# MyRollerShutter_rfm_1-3.net
KiCad netlist of a schematic drawn in EAGLE
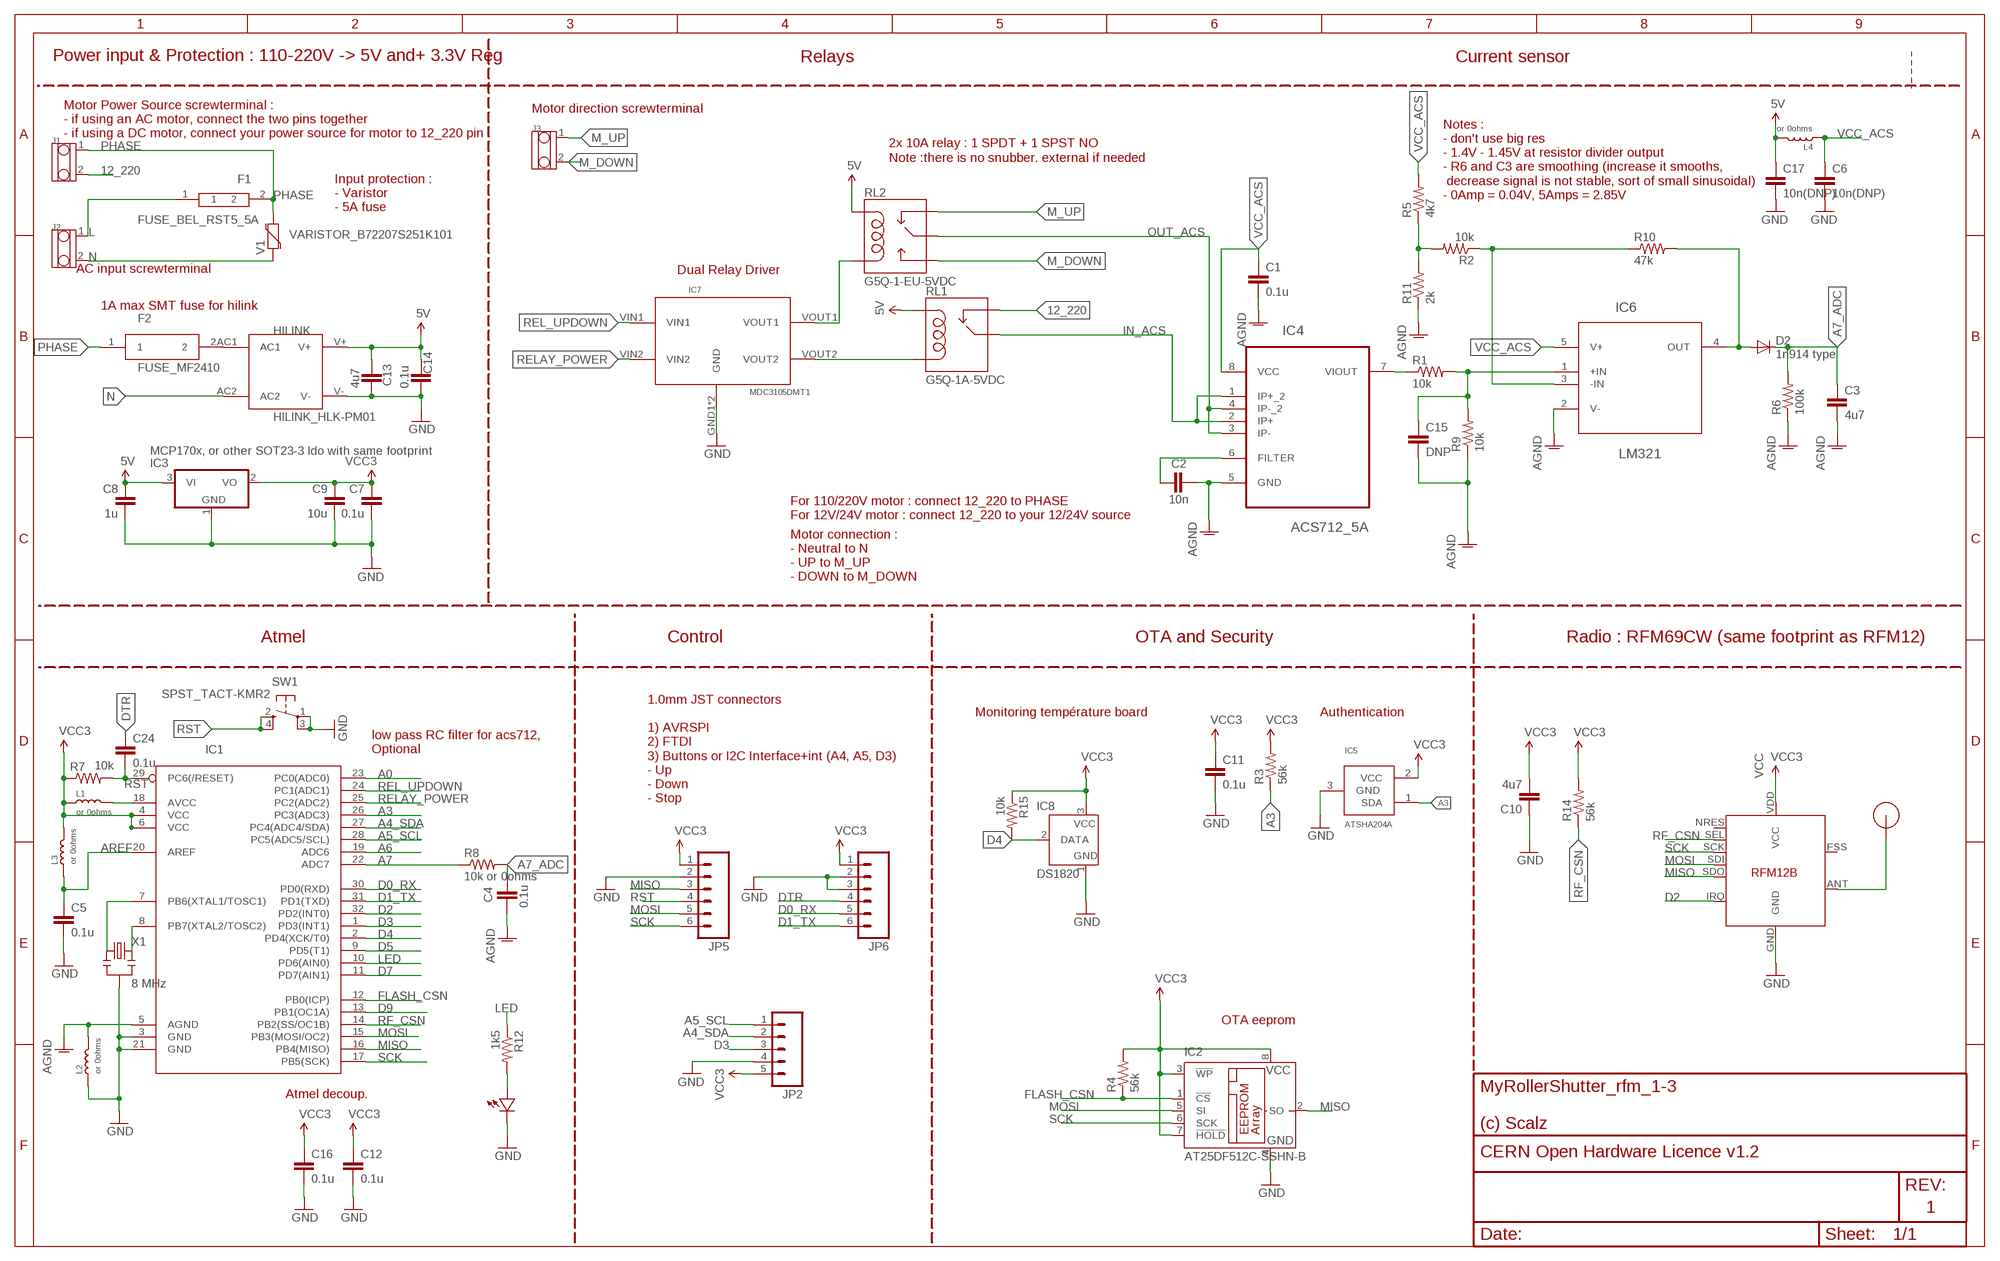
[diagram p0: schematic, sheet 1]

(export (version "E")
  (design (tool "Eeschema 10.0.6"))
  (components
    (comp (ref "ANT")
      (value "RFM12B_ANTENNA")
      (footprint "eagle-import:RFM12B-ANTENNA")
      (libsource (lib "eagle-import") (part "RFM12B_ANTENNA"))
    )
    (comp (ref "C1")
      (value "0.1u")
      (footprint "eagle-import:0805-CAP")
      (libsource (lib "eagle-import") (part "CAP0805-CAP"))
    )
    (comp (ref "C2")
      (value "10n")
      (footprint "eagle-import:0805-CAP")
      (libsource (lib "eagle-import") (part "CAP0805-CAP"))
    )
    (comp (ref "C3")
      (value "4u7")
      (footprint "eagle-import:0805-CAP")
      (libsource (lib "eagle-import") (part "CAP0805-CAP"))
    )
    (comp (ref "C4")
      (value "0.1u")
      (footprint "eagle-import:0805-CAP")
      (libsource (lib "eagle-import") (part "CAP0805-CAP"))
    )
    (comp (ref "C5")
      (value "0.1u")
      (footprint "eagle-import:0805-CAP")
      (libsource (lib "eagle-import") (part "CAP0805-CAP"))
    )
    (comp (ref "C6")
      (value "10n(DNP)")
      (footprint "eagle-import:0805-CAP")
      (libsource (lib "eagle-import") (part "CAP0805-CAP"))
    )
    (comp (ref "C7")
      (value "0.1u")
      (footprint "eagle-import:0805-CAP")
      (libsource (lib "eagle-import") (part "CAP0805-CAP"))
    )
    (comp (ref "C8")
      (value "1u")
      (footprint "eagle-import:0805-CAP")
      (libsource (lib "eagle-import") (part "CAP0805-CAP"))
    )
    (comp (ref "C9")
      (value "10u")
      (footprint "eagle-import:0805-CAP")
      (libsource (lib "eagle-import") (part "CAP0805-CAP"))
    )
    (comp (ref "C10")
      (value "4u7")
      (footprint "eagle-import:0805-CAP")
      (libsource (lib "eagle-import") (part "CAP0805-CAP"))
    )
    (comp (ref "C11")
      (value "0.1u")
      (footprint "eagle-import:0805-CAP")
      (libsource (lib "eagle-import") (part "CAP0805-CAP"))
    )
    (comp (ref "C12")
      (value "0.1u")
      (footprint "eagle-import:0805-CAP")
      (libsource (lib "eagle-import") (part "CAP0805-CAP"))
    )
    (comp (ref "C13")
      (value "4u7")
      (footprint "eagle-import:0805-CAP")
      (libsource (lib "eagle-import") (part "CAP0805-CAP"))
    )
    (comp (ref "C14")
      (value "0.1u")
      (footprint "eagle-import:0805-CAP")
      (libsource (lib "eagle-import") (part "CAP0805-CAP"))
    )
    (comp (ref "C15")
      (value "DNP")
      (footprint "eagle-import:0805-CAP")
      (libsource (lib "eagle-import") (part "CAP0805-CAP"))
    )
    (comp (ref "C16")
      (value "0.1u")
      (footprint "eagle-import:0805-CAP")
      (libsource (lib "eagle-import") (part "CAP0805-CAP"))
    )
    (comp (ref "C17")
      (value "10n(DNP)")
      (footprint "eagle-import:0805-CAP")
      (libsource (lib "eagle-import") (part "CAP0805-CAP"))
    )
    (comp (ref "C24")
      (value "0.1u")
      (footprint "eagle-import:0805-CAP")
      (libsource (lib "eagle-import") (part "CAP0805-CAP"))
    )
    (comp (ref "D1")
      (value "LED0805")
      (footprint "eagle-import:0805-LED")
      (libsource (lib "eagle-import") (part "LED0805"))
    )
    (comp (ref "D2")
      (value "1n914 type")
      (footprint "eagle-import:SOD-323")
      (libsource (lib "eagle-import") (part "DIODESOD"))
    )
    (comp (ref "F1")
      (value "FUSE_BEL_RST5_5A")
      (footprint "eagle-import:FUSE_BEL_RST5_5A")
      (libsource (lib "eagle-import") (part "FUSE_BEL_RST5_5A"))
    )
    (comp (ref "F2")
      (value "FUSE_MF2410")
      (footprint "eagle-import:2410")
      (libsource (lib "eagle-import") (part "FUSE_MF2410"))
    )
    (comp (ref "HILINK")
      (value "HILINK_HLK-PM01")
      (footprint "eagle-import:HILINK_HLK-PM01")
      (libsource (lib "eagle-import") (part "HILINK_HLK-PM01"))
    )
    (comp (ref "IC1")
      (value "ATMega-328")
      (footprint "eagle-import:TQFP32-08")
      (libsource (lib "eagle-import") (part "ATMEGA168/328TQFP32"))
    )
    (comp (ref "IC2")
      (value "AT25DF512C-SSHN-B")
      (footprint "eagle-import:SO-08")
      (fields (field (name "MF") "MICROCHIP") (field (name "MPN") "25AA080/SN"))
      (libsource (lib "eagle-import") (part "25SNAA080"))
    )
    (comp (ref "IC3")
      (value "MCP170x, or other SOT23-3 ldo with same footprint")
      (footprint "eagle-import:SOT23")
      (libsource (lib "eagle-import") (part "MCP1703CB"))
    )
    (comp (ref "IC4")
      (value "ACS712_5A")
      (footprint "eagle-import:SOIC127P600X175-8N")
      (fields (field (name "MPN") "ACS712ELCTR-20A-T"))
      (libsource (lib "eagle-import") (part "ACS712ELCTR-20A-T"))
    )
    (comp (ref "IC5")
      (value "ATSHA204A")
      (footprint "eagle-import:SOT23")
      (libsource (lib "eagle-import") (part "ATSHA204A"))
    )
    (comp (ref "IC6")
      (value "LM321")
      (footprint "eagle-import:SOT95P285X120-5N")
      (fields (field (name "MPN") "LM321MF"))
      (libsource (lib "eagle-import") (part "LM321MF"))
    )
    (comp (ref "IC7")
      (value "MDC3105DMT1")
      (footprint "eagle-import:MDC3105DMT1")
      (libsource (lib "eagle-import") (part "MDC3105DMT1"))
    )
    (comp (ref "IC8")
      (value "DS1820")
      (footprint "eagle-import:TO92-")
      (libsource (lib "eagle-import") (part "DS1820"))
    )
    (comp (ref "J1")
      (value "SCREW-TERMINAL-2P-3470110P1")
      (footprint "eagle-import:2P-5.0")
      (libsource (lib "eagle-import") (part "SCREW-TERMINAL-2P-3470110P1"))
    )
    (comp (ref "J2")
      (value "SCREW-TERMINAL-2P-3470110P1")
      (footprint "eagle-import:2P-5.0")
      (libsource (lib "eagle-import") (part "SCREW-TERMINAL-2P-3470110P1"))
    )
    (comp (ref "J3")
      (value "SCREW-TERMINAL-2P-3470110P1")
      (footprint "eagle-import:2P-5.0")
      (libsource (lib "eagle-import") (part "SCREW-TERMINAL-2P-3470110P1"))
    )
    (comp (ref "JP2")
      (value "M05SMD")
      (footprint "eagle-import:1X05-1MM")
      (libsource (lib "eagle-import") (part "M05SMD"))
    )
    (comp (ref "JP5")
      (value "M06SMD-1MM")
      (footprint "eagle-import:1X06-1MM")
      (libsource (lib "eagle-import") (part "M06SMD-1MM"))
    )
    (comp (ref "JP6")
      (value "M06SMD-1MM")
      (footprint "eagle-import:1X06-1MM")
      (libsource (lib "eagle-import") (part "M06SMD-1MM"))
    )
    (comp (ref "L1")
      (value "or 0ohms")
      (footprint "eagle-import:L0805")
      (libsource (lib "eagle-import") (part "INDUCTOR/FERRITE-BEAD-0805"))
    )
    (comp (ref "L2")
      (value "or 0ohms")
      (footprint "eagle-import:L0805")
      (libsource (lib "eagle-import") (part "INDUCTOR/FERRITE-BEAD-0805"))
    )
    (comp (ref "L3")
      (value "or 0ohms")
      (footprint "eagle-import:L0805")
      (libsource (lib "eagle-import") (part "INDUCTOR/FERRITE-BEAD-0805"))
    )
    (comp (ref "L4")
      (value "or 0ohms")
      (footprint "eagle-import:L0805")
      (libsource (lib "eagle-import") (part "INDUCTOR/FERRITE-BEAD-0805"))
    )
    (comp (ref "R1")
      (value "10k")
      (footprint "eagle-import:0805-RES")
      (libsource (lib "eagle-import") (part "RESISTOR0805-RES"))
    )
    (comp (ref "R2")
      (value "10k")
      (footprint "eagle-import:0805-RES")
      (libsource (lib "eagle-import") (part "RESISTOR0805-RES"))
    )
    (comp (ref "R3")
      (value "56k")
      (footprint "eagle-import:0805-RES")
      (libsource (lib "eagle-import") (part "RESISTOR0805-RES"))
    )
    (comp (ref "R4")
      (value "56k")
      (footprint "eagle-import:0805-RES")
      (libsource (lib "eagle-import") (part "RESISTOR0805-RES"))
    )
    (comp (ref "R5")
      (value "4k7")
      (footprint "eagle-import:0805-RES")
      (libsource (lib "eagle-import") (part "RESISTOR0805-RES"))
    )
    (comp (ref "R6")
      (value "100k")
      (footprint "eagle-import:0805-RES")
      (libsource (lib "eagle-import") (part "RESISTOR0805-RES"))
    )
    (comp (ref "R7")
      (value "10k")
      (footprint "eagle-import:0805-RES")
      (libsource (lib "eagle-import") (part "RESISTOR0805-RES"))
    )
    (comp (ref "R8")
      (value "10k or 0ohms")
      (footprint "eagle-import:0805-RES")
      (libsource (lib "eagle-import") (part "RESISTOR0805-RES"))
    )
    (comp (ref "R9")
      (value "10k")
      (footprint "eagle-import:0805-RES")
      (libsource (lib "eagle-import") (part "RESISTOR0805-RES"))
    )
    (comp (ref "R10")
      (value "47k")
      (footprint "eagle-import:0805-RES")
      (libsource (lib "eagle-import") (part "RESISTOR0805-RES"))
    )
    (comp (ref "R11")
      (value "2k")
      (footprint "eagle-import:0805-RES")
      (libsource (lib "eagle-import") (part "RESISTOR0805-RES"))
    )
    (comp (ref "R12")
      (value "1k5")
      (footprint "eagle-import:0805-RES")
      (libsource (lib "eagle-import") (part "RESISTOR0805-RES"))
    )
    (comp (ref "R14")
      (value "56k")
      (footprint "eagle-import:0805-RES")
      (libsource (lib "eagle-import") (part "RESISTOR0805-RES"))
    )
    (comp (ref "R15")
      (value "10k")
      (footprint "eagle-import:0805-RES")
      (libsource (lib "eagle-import") (part "RESISTOR0805-RES"))
    )
    (comp (ref "RFM69CW")
      (value "RFM69CW")
      (footprint "eagle-import:RFM12B-MINPADS")
      (libsource (lib "eagle-import") (part "RFM12B"))
    )
    (comp (ref "RL1")
      (value "G5Q-1A-5VDC")
      (footprint "eagle-import:G5Q_SINGLE")
      (libsource (lib "eagle-import") (part "G5Q_SINGLE"))
    )
    (comp (ref "RL2")
      (value "G5Q-1-EU-5VDC")
      (footprint "eagle-import:RELAY-G5Q")
      (libsource (lib "eagle-import") (part "RELAYPTH"))
    )
    (comp (ref "SW1")
      (value "SPST_TACT-KMR2")
      (footprint "eagle-import:KMR2")
      (libsource (lib "eagle-import") (part "SPST_TACT-KMR2"))
    )
    (comp (ref "V1")
      (value "VARISTOR_B72207S251K101")
      (footprint "eagle-import:VARISTOR_B72207S251K101")
      (libsource (lib "eagle-import") (part "VARISTOR_B72207S251K101"))
    )
    (comp (ref "X1")
      (value "8 MHz")
      (footprint "eagle-import:RESONATOR-SMD")
      (libsource (lib "eagle-import") (part "RESONATORSMD"))
    )
  )
  (nets
    (net (code "1") (name "/A0") (class "Default")
      (node (ref "IC1") (pin "23") (pinfunction "PC0(ADC0)_23") (pintype "bidirectional"))
    )
    (net (code "2") (name "/A4_SDA") (class "Default")
      (node (ref "IC1") (pin "27") (pinfunction "PC4(ADC4/SDA)_27") (pintype "bidirectional"))
      (node (ref "JP2") (pin "2") (pinfunction "2_2") (pintype "passive"))
    )
    (net (code "3") (name "/A5_SCL") (class "Default")
      (node (ref "IC1") (pin "28") (pinfunction "PC5(ADC5/SCL)_28") (pintype "bidirectional"))
      (node (ref "JP2") (pin "1") (pinfunction "1_1") (pintype "passive"))
    )
    (net (code "4") (name "/A6") (class "Default")
      (node (ref "IC1") (pin "19") (pinfunction "ADC6_19") (pintype "bidirectional"))
    )
    (net (code "5") (name "/A7") (class "Default")
      (node (ref "IC1") (pin "22") (pinfunction "ADC7_22") (pintype "bidirectional"))
      (node (ref "R8") (pin "1") (pinfunction "1_1") (pintype "passive"))
    )
    (net (code "6") (name "/AREF") (class "Default")
      (node (ref "C5") (pin "1") (pinfunction "1_1") (pintype "passive"))
      (node (ref "IC1") (pin "20") (pinfunction "AREF_20") (pintype "bidirectional"))
      (node (ref "L3") (pin "1") (pinfunction "1_1") (pintype "passive"))
    )
    (net (code "7") (name "/D0_RX") (class "Default")
      (node (ref "IC1") (pin "30") (pinfunction "PD0(RXD)_30") (pintype "bidirectional"))
      (node (ref "JP6") (pin "5") (pinfunction "5_5") (pintype "passive"))
    )
    (net (code "8") (name "/D1_TX") (class "Default")
      (node (ref "IC1") (pin "31") (pinfunction "PD1(TXD)_31") (pintype "bidirectional"))
      (node (ref "JP6") (pin "6") (pinfunction "6_6") (pintype "passive"))
    )
    (net (code "9") (name "/D2") (class "Default")
      (node (ref "IC1") (pin "32") (pinfunction "PD2(INT0)_32") (pintype "bidirectional"))
      (node (ref "RFM69CW") (pin "IRQ") (pinfunction "IRQ_IRQ") (pintype "open_collector"))
    )
    (net (code "10") (name "/D3") (class "Default")
      (node (ref "IC1") (pin "1") (pinfunction "PD3(INT1)_1") (pintype "bidirectional"))
      (node (ref "JP2") (pin "3") (pinfunction "3_3") (pintype "passive"))
    )
    (net (code "11") (name "/D5") (class "Default")
      (node (ref "IC1") (pin "9") (pinfunction "PD5(T1)_9") (pintype "bidirectional"))
    )
    (net (code "12") (name "/D7") (class "Default")
      (node (ref "IC1") (pin "11") (pinfunction "PD7(AIN1)_11") (pintype "bidirectional"))
    )
    (net (code "13") (name "/D9") (class "Default")
      (node (ref "IC1") (pin "13") (pinfunction "PB1(OC1A)_13") (pintype "bidirectional"))
    )
    (net (code "14") (name "/FLASH_CSN") (class "Default")
      (node (ref "IC1") (pin "12") (pinfunction "PB0(ICP)_12") (pintype "bidirectional"))
      (node (ref "IC2") (pin "1") (pinfunction "~{CS}_1") (pintype "input"))
      (node (ref "R4") (pin "1") (pinfunction "1_1") (pintype "passive"))
    )
    (net (code "15") (name "/IN_ACS") (class "Default")
      (node (ref "IC4") (pin "1") (pinfunction "IP+_2_1") (pintype "input"))
      (node (ref "IC4") (pin "2") (pinfunction "IP+_2") (pintype "input"))
      (node (ref "RL1") (pin "2") (pinfunction "MAIN_2") (pintype "bidirectional"))
    )
    (net (code "16") (name "/L") (class "Default")
      (node (ref "F1") (pin "1") (pinfunction "1_1") (pintype "bidirectional"))
      (node (ref "J2") (pin "1") (pinfunction "1_1") (pintype "bidirectional"))
    )
    (net (code "17") (name "/LED") (class "Default")
      (node (ref "IC1") (pin "10") (pinfunction "PD6(AIN0)_10") (pintype "bidirectional"))
      (node (ref "R12") (pin "1") (pinfunction "1_1") (pintype "passive"))
    )
    (net (code "18") (name "/MISO") (class "Default")
      (node (ref "IC1") (pin "16") (pinfunction "PB4(MISO)_16") (pintype "bidirectional"))
      (node (ref "IC2") (pin "2") (pinfunction "SO_2") (pintype "bidirectional"))
      (node (ref "JP5") (pin "3") (pinfunction "3_3") (pintype "passive"))
      (node (ref "RFM69CW") (pin "SDO") (pinfunction "SDO_SDO") (pintype "output"))
    )
    (net (code "19") (name "/MOSI") (class "Default")
      (node (ref "IC1") (pin "15") (pinfunction "PB3(MOSI/OC2)_15") (pintype "bidirectional"))
      (node (ref "IC2") (pin "5") (pinfunction "SI_5") (pintype "input"))
      (node (ref "JP5") (pin "5") (pinfunction "5_5") (pintype "passive"))
      (node (ref "RFM69CW") (pin "SDI") (pinfunction "SDI_SDI") (pintype "input"))
    )
    (net (code "20") (name "/OUT_ACS") (class "Default")
      (node (ref "IC4") (pin "3") (pinfunction "IP-_3") (pintype "input"))
      (node (ref "IC4") (pin "4") (pinfunction "IP-_2_4") (pintype "input"))
      (node (ref "RL2") (pin "2") (pinfunction "MAIN_2") (pintype "bidirectional"))
    )
    (net (code "21") (name "/SCK") (class "Default")
      (node (ref "IC1") (pin "17") (pinfunction "PB5(SCK)_17") (pintype "bidirectional"))
      (node (ref "IC2") (pin "6") (pinfunction "SCK_6") (pintype "input"))
      (node (ref "JP5") (pin "6") (pinfunction "6_6") (pintype "passive"))
      (node (ref "RFM69CW") (pin "SCK") (pinfunction "SCK_SCK") (pintype "input"))
    )
    (net (code "22") (name "5V") (class "Default")
      (node (ref "C13") (pin "1") (pinfunction "1_1") (pintype "passive"))
      (node (ref "C14") (pin "1") (pinfunction "1_1") (pintype "passive"))
      (node (ref "C17") (pin "1") (pinfunction "1_1") (pintype "passive"))
      (node (ref "C8") (pin "1") (pinfunction "1_1") (pintype "passive"))
      (node (ref "HILINK") (pin "V+") (pinfunction "V+_V+") (pintype "bidirectional"))
      (node (ref "IC3") (pin "3") (pinfunction "VI_3") (pintype "input"))
      (node (ref "L4") (pin "2") (pinfunction "2_2") (pintype "passive"))
      (node (ref "RL1") (pin "1") (pinfunction "COIL1_1") (pintype "bidirectional"))
      (node (ref "RL2") (pin "5") (pinfunction "COIL1_5") (pintype "bidirectional"))
    )
    (net (code "23") (name "12_220") (class "Default")
      (node (ref "J1") (pin "2") (pinfunction "2_2") (pintype "bidirectional"))
      (node (ref "RL1") (pin "3") (pinfunction "NC_3") (pintype "bidirectional"))
    )
    (net (code "24") (name "A3") (class "Default")
      (node (ref "IC1") (pin "26") (pinfunction "PC3(ADC3)_26") (pintype "bidirectional"))
      (node (ref "IC5") (pin "1") (pinfunction "SDA_1") (pintype "bidirectional"))
      (node (ref "R3") (pin "1") (pinfunction "1_1") (pintype "passive"))
    )
    (net (code "25") (name "A7_ADC") (class "Default")
      (node (ref "C3") (pin "1") (pinfunction "1_1") (pintype "passive"))
      (node (ref "C4") (pin "2") (pinfunction "2_2") (pintype "passive"))
      (node (ref "D2") (pin "1") (pinfunction "C_1") (pintype "passive"))
      (node (ref "R6") (pin "2") (pinfunction "2_2") (pintype "passive"))
      (node (ref "R8") (pin "2") (pinfunction "2_2") (pintype "passive"))
    )
    (net (code "26") (name "AGND") (class "Default")
      (node (ref "C1") (pin "2") (pinfunction "2_2") (pintype "passive"))
      (node (ref "C15") (pin "2") (pinfunction "2_2") (pintype "passive"))
      (node (ref "C2") (pin "2") (pinfunction "2_2") (pintype "passive"))
      (node (ref "C3") (pin "2") (pinfunction "2_2") (pintype "passive"))
      (node (ref "C4") (pin "1") (pinfunction "1_1") (pintype "passive"))
      (node (ref "IC1") (pin "5") (pinfunction "AGND_5") (pintype "bidirectional"))
      (node (ref "IC4") (pin "5") (pinfunction "GND_5") (pintype "passive"))
      (node (ref "IC6") (pin "2") (pinfunction "V-_2") (pintype "power_in"))
      (node (ref "L2") (pin "2") (pinfunction "2_2") (pintype "passive"))
      (node (ref "R11") (pin "1") (pinfunction "1_1") (pintype "passive"))
      (node (ref "R6") (pin "1") (pinfunction "1_1") (pintype "passive"))
      (node (ref "R9") (pin "1") (pinfunction "1_1") (pintype "passive"))
    )
    (net (code "27") (name "D4") (class "Default")
      (node (ref "IC1") (pin "2") (pinfunction "PD4(XCK/T0)_2") (pintype "bidirectional"))
      (node (ref "IC8") (pin "2") (pinfunction "DATA_2") (pintype "input"))
      (node (ref "R15") (pin "2") (pinfunction "2_2") (pintype "passive"))
    )
    (net (code "28") (name "DTR") (class "Default")
      (node (ref "C24") (pin "1") (pinfunction "1_1") (pintype "passive"))
      (node (ref "JP6") (pin "4") (pinfunction "4_4") (pintype "passive"))
    )
    (net (code "29") (name "GND") (class "Default")
      (node (ref "C10") (pin "1") (pinfunction "1_1") (pintype "passive"))
      (node (ref "C11") (pin "2") (pinfunction "2_2") (pintype "passive"))
      (node (ref "C12") (pin "2") (pinfunction "2_2") (pintype "passive"))
      (node (ref "C13") (pin "2") (pinfunction "2_2") (pintype "passive"))
      (node (ref "C14") (pin "2") (pinfunction "2_2") (pintype "passive"))
      (node (ref "C16") (pin "2") (pinfunction "2_2") (pintype "passive"))
      (node (ref "C17") (pin "2") (pinfunction "2_2") (pintype "passive"))
      (node (ref "C5") (pin "2") (pinfunction "2_2") (pintype "passive"))
      (node (ref "C6") (pin "2") (pinfunction "2_2") (pintype "passive"))
      (node (ref "C7") (pin "2") (pinfunction "2_2") (pintype "passive"))
      (node (ref "C8") (pin "2") (pinfunction "2_2") (pintype "passive"))
      (node (ref "C9") (pin "2") (pinfunction "2_2") (pintype "passive"))
      (node (ref "D1") (pin "MINUS") (pinfunction "MINUS_MINUS") (pintype "passive"))
      (node (ref "HILINK") (pin "V-") (pinfunction "V-_V-") (pintype "bidirectional"))
      (node (ref "IC1") (pin "21") (pinfunction "GND_21") (pintype "bidirectional"))
      (node (ref "IC1") (pin "3") (pinfunction "GND_3") (pintype "bidirectional"))
      (node (ref "IC2") (pin "4") (pinfunction "GND_4") (pintype "power_in"))
      (node (ref "IC3") (pin "1") (pinfunction "GND_1") (pintype "passive"))
      (node (ref "IC5") (pin "3") (pinfunction "GND_3") (pintype "bidirectional"))
      (node (ref "IC7") (pin "GND1") (pinfunction "GND_GND1") (pintype "bidirectional"))
      (node (ref "IC7") (pin "GND2") (pinfunction "GND_GND2") (pintype "bidirectional"))
      (node (ref "IC8") (pin "1") (pinfunction "GND_1") (pintype "passive"))
      (node (ref "JP2") (pin "4") (pinfunction "4_4") (pintype "passive"))
      (node (ref "JP5") (pin "2") (pinfunction "2_2") (pintype "passive"))
      (node (ref "JP6") (pin "2") (pinfunction "2_2") (pintype "passive"))
      (node (ref "JP6") (pin "3") (pinfunction "3_3") (pintype "passive"))
      (node (ref "L2") (pin "1") (pinfunction "1_1") (pintype "passive"))
      (node (ref "RFM69CW") (pin "GND") (pinfunction "GND_GND") (pintype "power_in"))
      (node (ref "SW1") (pin "1") (pinfunction "P_1") (pintype "passive"))
      (node (ref "SW1") (pin "3") (pinfunction "P1_3") (pintype "passive"))
      (node (ref "X1") (pin "2") (pinfunction "2_2") (pintype "passive"))
    )
    (net (code "30") (name "M_DOWN") (class "Default")
      (node (ref "J3") (pin "2") (pinfunction "2_2") (pintype "bidirectional"))
      (node (ref "RL2") (pin "3") (pinfunction "NO_3") (pintype "bidirectional"))
    )
    (net (code "31") (name "M_UP") (class "Default")
      (node (ref "J3") (pin "1") (pinfunction "1_1") (pintype "bidirectional"))
      (node (ref "RL2") (pin "4") (pinfunction "NC_4") (pintype "bidirectional"))
    )
    (net (code "32") (name "N") (class "Default")
      (node (ref "HILINK") (pin "AC2") (pinfunction "AC2_AC2") (pintype "bidirectional"))
      (node (ref "J2") (pin "2") (pinfunction "2_2") (pintype "bidirectional"))
      (node (ref "V1") (pin "1") (pinfunction "1_1") (pintype "passive"))
    )
    (net (code "33") (name "Net-(ANT-1)") (class "Default")
      (node (ref "ANT") (pin "P$1") (pinfunction "1_P$1") (pintype "bidirectional"))
      (node (ref "RFM69CW") (pin "ANT") (pinfunction "ANT_ANT") (pintype "passive"))
    )
    (net (code "34") (name "Net-(D1-PadPLUS)") (class "Default")
      (node (ref "D1") (pin "PLUS") (pinfunction "PLUS_PLUS") (pintype "passive"))
      (node (ref "R12") (pin "2") (pinfunction "2_2") (pintype "passive"))
    )
    (net (code "35") (name "Net-(D2-A)") (class "Default")
      (node (ref "D2") (pin "2") (pinfunction "A_2") (pintype "passive"))
      (node (ref "IC6") (pin "4") (pinfunction "OUT_4") (pintype "output"))
      (node (ref "R10") (pin "2") (pinfunction "2_2") (pintype "passive"))
    )
    (net (code "36") (name "Net-(F2-Pad2)") (class "Default")
      (node (ref "F2") (pin "2") (pinfunction "2_2") (pintype "bidirectional"))
      (node (ref "HILINK") (pin "AC1") (pinfunction "AC1_AC1") (pintype "bidirectional"))
    )
    (net (code "37") (name "Net-(IC1-AVCC)") (class "Default")
      (node (ref "IC1") (pin "18") (pinfunction "AVCC_18") (pintype "bidirectional"))
      (node (ref "L1") (pin "2") (pinfunction "2_2") (pintype "passive"))
    )
    (net (code "38") (name "Net-(IC1-PB6(XTAL1{slash}TOSC1))") (class "Default")
      (node (ref "IC1") (pin "7") (pinfunction "PB6(XTAL1/TOSC1)_7") (pintype "bidirectional"))
      (node (ref "X1") (pin "1") (pinfunction "1_1") (pintype "passive"))
    )
    (net (code "39") (name "Net-(IC1-PB7(XTAL2{slash}TOSC2))") (class "Default")
      (node (ref "IC1") (pin "8") (pinfunction "PB7(XTAL2/TOSC2)_8") (pintype "bidirectional"))
      (node (ref "X1") (pin "3") (pinfunction "3_3") (pintype "passive"))
    )
    (net (code "40") (name "Net-(IC4-FILTER)") (class "Default")
      (node (ref "C2") (pin "1") (pinfunction "1_1") (pintype "passive"))
      (node (ref "IC4") (pin "6") (pinfunction "FILTER_6") (pintype "input"))
    )
    (net (code "41") (name "Net-(IC4-VIOUT)") (class "Default")
      (node (ref "IC4") (pin "7") (pinfunction "VIOUT_7") (pintype "output"))
      (node (ref "R1") (pin "1") (pinfunction "1_1") (pintype "passive"))
    )
    (net (code "42") (name "Net-(IC6-+IN)") (class "Default")
      (node (ref "C15") (pin "1") (pinfunction "1_1") (pintype "passive"))
      (node (ref "IC6") (pin "1") (pinfunction "+IN_1") (pintype "input"))
      (node (ref "R1") (pin "2") (pinfunction "2_2") (pintype "passive"))
      (node (ref "R9") (pin "2") (pinfunction "2_2") (pintype "passive"))
    )
    (net (code "43") (name "Net-(IC6--IN)") (class "Default")
      (node (ref "IC6") (pin "3") (pinfunction "-IN_3") (pintype "input"))
      (node (ref "R10") (pin "1") (pinfunction "1_1") (pintype "passive"))
      (node (ref "R2") (pin "1") (pinfunction "1_1") (pintype "passive"))
    )
    (net (code "44") (name "Net-(R11-Pad2)") (class "Default")
      (node (ref "R11") (pin "2") (pinfunction "2_2") (pintype "passive"))
      (node (ref "R2") (pin "2") (pinfunction "2_2") (pintype "passive"))
      (node (ref "R5") (pin "1") (pinfunction "1_1") (pintype "passive"))
    )
    (net (code "45") (name "Net-(RL1-COIL2)") (class "Default")
      (node (ref "IC7") (pin "VOUT2") (pinfunction "VOUT2_VOUT2") (pintype "bidirectional"))
      (node (ref "RL1") (pin "5") (pinfunction "COIL2_5") (pintype "bidirectional"))
    )
    (net (code "46") (name "Net-(RL2-COIL2)") (class "Default")
      (node (ref "IC7") (pin "VOUT1") (pinfunction "VOUT1_VOUT1") (pintype "bidirectional"))
      (node (ref "RL2") (pin "1") (pinfunction "COIL2_1") (pintype "bidirectional"))
    )
    (net (code "47") (name "PHASE") (class "Default")
      (node (ref "F1") (pin "2") (pinfunction "2_2") (pintype "bidirectional"))
      (node (ref "F2") (pin "1") (pinfunction "1_1") (pintype "bidirectional"))
      (node (ref "J1") (pin "1") (pinfunction "1_1") (pintype "bidirectional"))
      (node (ref "V1") (pin "2") (pinfunction "2_2") (pintype "passive"))
    )
    (net (code "48") (name "RELAY_POWER") (class "Default")
      (node (ref "IC1") (pin "25") (pinfunction "PC2(ADC2)_25") (pintype "bidirectional"))
      (node (ref "IC7") (pin "VIN2") (pinfunction "VIN2_VIN2") (pintype "bidirectional"))
    )
    (net (code "49") (name "REL_UPDOWN") (class "Default")
      (node (ref "IC1") (pin "24") (pinfunction "PC1(ADC1)_24") (pintype "bidirectional"))
      (node (ref "IC7") (pin "VIN1") (pinfunction "VIN1_VIN1") (pintype "bidirectional"))
    )
    (net (code "50") (name "RF_CSN") (class "Default")
      (node (ref "IC1") (pin "14") (pinfunction "PB2(SS/OC1B)_14") (pintype "bidirectional"))
      (node (ref "R14") (pin "1") (pinfunction "1_1") (pintype "passive"))
      (node (ref "RFM69CW") (pin "SEL") (pinfunction "SEL_SEL") (pintype "input"))
    )
    (net (code "51") (name "RST") (class "Default")
      (node (ref "C24") (pin "2") (pinfunction "2_2") (pintype "passive"))
      (node (ref "IC1") (pin "29") (pinfunction "PC6(/RESET)_29") (pintype "bidirectional"))
      (node (ref "JP5") (pin "4") (pinfunction "4_4") (pintype "passive"))
      (node (ref "R7") (pin "2") (pinfunction "2_2") (pintype "passive"))
      (node (ref "SW1") (pin "2") (pinfunction "S_2") (pintype "passive"))
      (node (ref "SW1") (pin "4") (pinfunction "S1_4") (pintype "passive"))
    )
    (net (code "52") (name "VCC3") (class "Default")
      (node (ref "C10") (pin "2") (pinfunction "2_2") (pintype "passive"))
      (node (ref "C11") (pin "1") (pinfunction "1_1") (pintype "passive"))
      (node (ref "C12") (pin "1") (pinfunction "1_1") (pintype "passive"))
      (node (ref "C16") (pin "1") (pinfunction "1_1") (pintype "passive"))
      (node (ref "C7") (pin "1") (pinfunction "1_1") (pintype "passive"))
      (node (ref "C9") (pin "1") (pinfunction "1_1") (pintype "passive"))
      (node (ref "IC1") (pin "4") (pinfunction "VCC_4") (pintype "bidirectional"))
      (node (ref "IC1") (pin "6") (pinfunction "VCC_6") (pintype "bidirectional"))
      (node (ref "IC2") (pin "3") (pinfunction "~{WP}_3") (pintype "input"))
      (node (ref "IC2") (pin "7") (pinfunction "~{HOLD}_7") (pintype "input"))
      (node (ref "IC2") (pin "8") (pinfunction "VCC_8") (pintype "power_in"))
      (node (ref "IC3") (pin "2") (pinfunction "VO_2") (pintype "passive"))
      (node (ref "IC5") (pin "2") (pinfunction "VCC_2") (pintype "bidirectional"))
      (node (ref "IC8") (pin "3") (pinfunction "VCC_3") (pintype "passive"))
      (node (ref "JP2") (pin "5") (pinfunction "5_5") (pintype "passive"))
      (node (ref "JP5") (pin "1") (pinfunction "1_1") (pintype "passive"))
      (node (ref "JP6") (pin "1") (pinfunction "1_1") (pintype "passive"))
      (node (ref "L1") (pin "1") (pinfunction "1_1") (pintype "passive"))
      (node (ref "L3") (pin "2") (pinfunction "2_2") (pintype "passive"))
      (node (ref "R14") (pin "2") (pinfunction "2_2") (pintype "passive"))
      (node (ref "R15") (pin "1") (pinfunction "1_1") (pintype "passive"))
      (node (ref "R3") (pin "2") (pinfunction "2_2") (pintype "passive"))
      (node (ref "R4") (pin "2") (pinfunction "2_2") (pintype "passive"))
      (node (ref "R7") (pin "1") (pinfunction "1_1") (pintype "passive"))
      (node (ref "RFM69CW") (pin "VDD") (pinfunction "VCC_VDD") (pintype "power_in"))
    )
    (net (code "53") (name "VCC_ACS") (class "Default")
      (node (ref "C1") (pin "1") (pinfunction "1_1") (pintype "passive"))
      (node (ref "C6") (pin "1") (pinfunction "1_1") (pintype "passive"))
      (node (ref "IC4") (pin "8") (pinfunction "VCC_8") (pintype "power_in"))
      (node (ref "IC6") (pin "5") (pinfunction "V+_5") (pintype "power_in"))
      (node (ref "L4") (pin "1") (pinfunction "1_1") (pintype "passive"))
      (node (ref "R5") (pin "2") (pinfunction "2_2") (pintype "passive"))
    )
    (net (code "54") (name "unconnected-(RFM69CW-FFS-PadFSS)") (class "Default")
      (node (ref "RFM69CW") (pin "FSS") (pinfunction "FFS_FSS") (pintype "bidirectional"))
    )
    (net (code "55") (name "unconnected-(RFM69CW-PadNRES)") (class "Default")
      (node (ref "RFM69CW") (pin "NRES") (pinfunction "NRES_NRES") (pintype "input"))
    )
  )
)
